# efr32_vna.net
KiCad netlist of a schematic drawn in Altium Designer
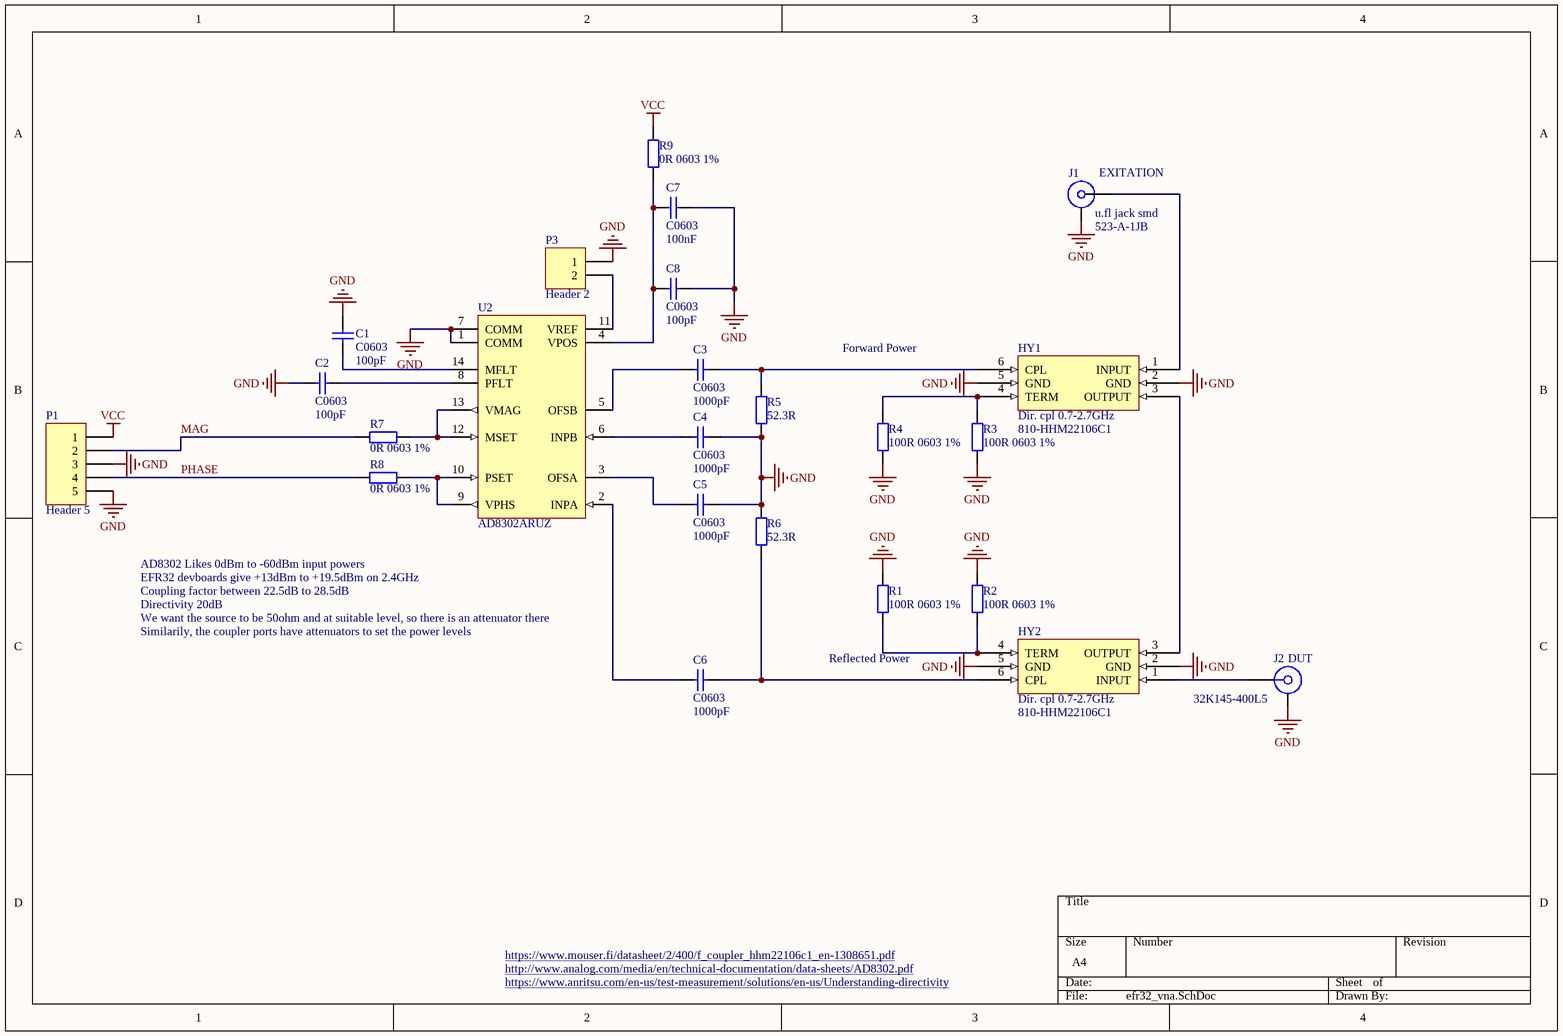
[diagram p0: efr32_vna.SchDoc]

(export (version "E")
  (design (tool "Eeschema 10.0.6"))
  (components
    (comp (ref "C1")
      (value "C0603")
      (footprint "0603")
      (description "Ceramic Chip Capacitor - Standard")
      (fields (field (name "ALTIUM_VALUE") "100pF") (field (name "PUBLISHER") "Altium Limited"))
      (libsource (lib "KEMET Chip Capacitor") (part "C0603"))
    )
    (comp (ref "C2")
      (value "C0603")
      (footprint "0603")
      (description "Ceramic Chip Capacitor - Standard")
      (fields (field (name "ALTIUM_VALUE") "100pF") (field (name "PUBLISHER") "Altium Limited"))
      (libsource (lib "KEMET Chip Capacitor") (part "C0603"))
    )
    (comp (ref "C3")
      (value "C0603")
      (footprint "0603")
      (description "Ceramic Chip Capacitor - Standard")
      (fields (field (name "ALTIUM_VALUE") "1000pF") (field (name "PUBLISHER") "Altium Limited"))
      (libsource (lib "KEMET Chip Capacitor") (part "C0603"))
    )
    (comp (ref "C4")
      (value "C0603")
      (footprint "0603")
      (description "Ceramic Chip Capacitor - Standard")
      (fields (field (name "ALTIUM_VALUE") "1000pF") (field (name "PUBLISHER") "Altium Limited"))
      (libsource (lib "KEMET Chip Capacitor") (part "C0603"))
    )
    (comp (ref "C5")
      (value "C0603")
      (footprint "0603")
      (description "Ceramic Chip Capacitor - Standard")
      (fields (field (name "ALTIUM_VALUE") "1000pF") (field (name "PUBLISHER") "Altium Limited"))
      (libsource (lib "KEMET Chip Capacitor") (part "C0603"))
    )
    (comp (ref "C6")
      (value "C0603")
      (footprint "0603")
      (description "Ceramic Chip Capacitor - Standard")
      (fields (field (name "ALTIUM_VALUE") "1000pF") (field (name "PUBLISHER") "Altium Limited"))
      (libsource (lib "KEMET Chip Capacitor") (part "C0603"))
    )
    (comp (ref "C7")
      (value "C0603")
      (footprint "0603")
      (description "Ceramic Chip Capacitor - Standard")
      (fields (field (name "ALTIUM_VALUE") "100nF") (field (name "PUBLISHER") "Altium Limited"))
      (libsource (lib "KEMET Chip Capacitor") (part "C0603"))
    )
    (comp (ref "C8")
      (value "C0603")
      (footprint "0603")
      (description "Ceramic Chip Capacitor - Standard")
      (fields (field (name "ALTIUM_VALUE") "100pF") (field (name "PUBLISHER") "Altium Limited"))
      (libsource (lib "KEMET Chip Capacitor") (part "C0603"))
    )
    (comp (ref "HY1")
      (value "Dir. cpl 0.7-2.7GHz")
      (footprint "1.6x0.8mm [EIA 0603]")
      (description "0.7-2.7GHz 28.5dB directional coupler")
      (fields (field (name "SUPPLIER PART NUMBER 1") "810-HHM22106C1"))
      (libsource (lib "") (part "HHM22106C1_1"))
    )
    (comp (ref "HY2")
      (value "Dir. cpl 0.7-2.7GHz")
      (footprint "1.6x0.8mm [EIA 0603]")
      (description "0.7-2.7GHz 28.5dB directional coupler")
      (fields (field (name "SUPPLIER PART NUMBER 1") "810-HHM22106C1"))
      (libsource (lib "ftg_lib") (part "HHM22106C1"))
    )
    (comp (ref "J1")
      (value "u.fl jack smd")
      (footprint "U.FL jack")
      (fields (field (name "SUPPLIER PART NUMBER 1") "523-A-1JB"))
      (libsource (lib "ftg_lib") (part "u.fl connector, jack A-1JB"))
    )
    (comp (ref "J2")
      (value "32K145-400L5")
      (footprint "ROS-32K145-400L5_V")
      (description "SMA Right Angle Jack, Edge Mount, Up to 18 GHz, -55 to 155 degC")
      (libsource (lib "Rosenberger SMA") (part "32K145-400L5"))
    )
    (comp (ref "P1")
      (value "Header 5")
      (footprint "HDR1X5")
      (description "Header, 5-Pin")
      (fields (field (name "PUBLISHER") "Altium Limited"))
      (libsource (lib "Miscellaneous Connectors") (part "Header 5"))
    )
    (comp (ref "P3")
      (value "Header 2")
      (footprint "HDR1X2")
      (description "Header, 2-Pin")
      (fields (field (name "PUBLISHER") "Altium Limited"))
      (libsource (lib "Miscellaneous Connectors") (part "Header 2"))
    )
    (comp (ref "R1")
      (value "100R 0603 1%")
      (footprint "R0603")
      (fields (field (name "TOLERANCE") "1%") (field (name "PUBLISHER") "iv"))
      (libsource (lib "ftg_lib") (part "100R 0603"))
    )
    (comp (ref "R2")
      (value "100R 0603 1%")
      (footprint "R0603")
      (fields (field (name "TOLERANCE") "1%") (field (name "PUBLISHER") "iv"))
      (libsource (lib "ftg_lib") (part "100R 0603"))
    )
    (comp (ref "R3")
      (value "100R 0603 1%")
      (footprint "R0603")
      (fields (field (name "TOLERANCE") "1%") (field (name "PUBLISHER") "iv"))
      (libsource (lib "") (part "100R 0603_1"))
    )
    (comp (ref "R4")
      (value "100R 0603 1%")
      (footprint "R0603")
      (fields (field (name "TOLERANCE") "1%") (field (name "PUBLISHER") "iv"))
      (libsource (lib "") (part "100R 0603_1"))
    )
    (comp (ref "R5")
      (value "52.3R")
      (footprint "R0603")
      (description "100R 0603 1%")
      (fields (field (name "TOLERANCE") "1%") (field (name "PUBLISHER") "iv"))
      (libsource (lib "ftg_lib") (part "100R 0603"))
    )
    (comp (ref "R6")
      (value "52.3R")
      (footprint "R0603")
      (description "100R 0603 1%")
      (fields (field (name "TOLERANCE") "1%") (field (name "PUBLISHER") "iv"))
      (libsource (lib "ftg_lib") (part "100R 0603"))
    )
    (comp (ref "R7")
      (value "0R 0603 1%")
      (footprint "R0603")
      (fields (field (name "TOLERANCE") "1%") (field (name "PUBLISHER") "iv"))
      (libsource (lib "ftg_lib") (part "0R 0603"))
    )
    (comp (ref "R8")
      (value "0R 0603 1%")
      (footprint "R0603")
      (fields (field (name "TOLERANCE") "1%") (field (name "PUBLISHER") "iv"))
      (libsource (lib "ftg_lib") (part "0R 0603"))
    )
    (comp (ref "R9")
      (value "0R 0603 1%")
      (footprint "R0603")
      (fields (field (name "TOLERANCE") "1%") (field (name "PUBLISHER") "iv"))
      (libsource (lib "") (part "0R 0603_1"))
    )
    (comp (ref "U2")
      (value "AD8302ARUZ")
      (footprint "ADI-RU-14_M")
      (description "LF-2.7 GHz RF/IF Gain and Phase Detector, 60ns Response Time, RU-14, Pb-Free, 96 Tube")
      (libsource (lib "Altium Content Vault") (part "ADI-AD8302-RU-14"))
    )
  )
  (nets
    (net (code "1") (name "/MAG") (class "Default")
      (node (ref "P1") (pin "2") (pinfunction "2_2") (pintype "passive"))
      (node (ref "R7") (pin "1") (pinfunction "1_1") (pintype "passive"))
    )
    (net (code "2") (name "/PHASE") (class "Default")
      (node (ref "P1") (pin "4") (pinfunction "4_4") (pintype "passive"))
      (node (ref "R8") (pin "1") (pinfunction "1_1") (pintype "passive"))
    )
    (net (code "3") (name "GND") (class "Default")
      (node (ref "C1") (pin "2") (pinfunction "2_2") (pintype "passive"))
      (node (ref "C2") (pin "1") (pinfunction "1_1") (pintype "passive"))
      (node (ref "C4") (pin "2") (pinfunction "2_2") (pintype "passive"))
      (node (ref "C5") (pin "2") (pinfunction "2_2") (pintype "passive"))
      (node (ref "C7") (pin "2") (pinfunction "2_2") (pintype "passive"))
      (node (ref "C8") (pin "2") (pinfunction "2_2") (pintype "passive"))
      (node (ref "HY1") (pin "2") (pinfunction "GND_2") (pintype "input"))
      (node (ref "HY1") (pin "5") (pinfunction "GND_5") (pintype "input"))
      (node (ref "HY2") (pin "2") (pinfunction "GND_2") (pintype "input"))
      (node (ref "HY2") (pin "5") (pinfunction "GND_5") (pintype "input"))
      (node (ref "J1") (pin "2") (pinfunction "2_2") (pintype "passive"))
      (node (ref "J2") (pin "MP") (pinfunction "MP_MP") (pintype "passive"))
      (node (ref "P1") (pin "3") (pinfunction "3_3") (pintype "passive"))
      (node (ref "P1") (pin "5") (pinfunction "5_5") (pintype "passive"))
      (node (ref "P3") (pin "1") (pinfunction "1_1") (pintype "passive"))
      (node (ref "R1") (pin "1") (pinfunction "1_1") (pintype "passive"))
      (node (ref "R2") (pin "1") (pinfunction "1_1") (pintype "passive"))
      (node (ref "R3") (pin "1") (pinfunction "1_1") (pintype "passive"))
      (node (ref "R4") (pin "1") (pinfunction "1_1") (pintype "passive"))
      (node (ref "R5") (pin "2") (pinfunction "2_2") (pintype "passive"))
      (node (ref "R6") (pin "1") (pinfunction "1_1") (pintype "passive"))
      (node (ref "U2") (pin "1") (pinfunction "COMM_1") (pintype "power_in"))
      (node (ref "U2") (pin "7") (pinfunction "COMM_7") (pintype "power_in"))
    )
    (net (code "4") (name "Net-(HY1-CPL)") (class "Default")
      (node (ref "C3") (pin "2") (pinfunction "2_2") (pintype "passive"))
      (node (ref "HY1") (pin "6") (pinfunction "CPL_6") (pintype "input"))
      (node (ref "R5") (pin "1") (pinfunction "1_1") (pintype "passive"))
    )
    (net (code "5") (name "Net-(HY1-INPUT)") (class "Default")
      (node (ref "HY1") (pin "1") (pinfunction "INPUT_1") (pintype "input"))
      (node (ref "J1") (pin "1") (pinfunction "1_1") (pintype "passive"))
    )
    (net (code "6") (name "Net-(HY1-OUTPUT)") (class "Default")
      (node (ref "HY1") (pin "3") (pinfunction "OUTPUT_3") (pintype "input"))
      (node (ref "HY2") (pin "3") (pinfunction "OUTPUT_3") (pintype "input"))
    )
    (net (code "7") (name "Net-(HY1-TERM)") (class "Default")
      (node (ref "HY1") (pin "4") (pinfunction "TERM_4") (pintype "input"))
      (node (ref "R3") (pin "2") (pinfunction "2_2") (pintype "passive"))
      (node (ref "R4") (pin "2") (pinfunction "2_2") (pintype "passive"))
    )
    (net (code "8") (name "Net-(HY2-CPL)") (class "Default")
      (node (ref "C6") (pin "2") (pinfunction "2_2") (pintype "passive"))
      (node (ref "HY2") (pin "6") (pinfunction "CPL_6") (pintype "input"))
      (node (ref "R6") (pin "2") (pinfunction "2_2") (pintype "passive"))
    )
    (net (code "9") (name "Net-(HY2-INPUT)") (class "Default")
      (node (ref "HY2") (pin "1") (pinfunction "INPUT_1") (pintype "input"))
      (node (ref "J2") (pin "1") (pinfunction "1_1") (pintype "passive"))
    )
    (net (code "10") (name "Net-(HY2-TERM)") (class "Default")
      (node (ref "HY2") (pin "4") (pinfunction "TERM_4") (pintype "input"))
      (node (ref "R1") (pin "2") (pinfunction "2_2") (pintype "passive"))
      (node (ref "R2") (pin "2") (pinfunction "2_2") (pintype "passive"))
    )
    (net (code "11") (name "Net-(U2-INPA)") (class "Default")
      (node (ref "C6") (pin "1") (pinfunction "1_1") (pintype "passive"))
      (node (ref "U2") (pin "2") (pinfunction "INPA_2") (pintype "input"))
    )
    (net (code "12") (name "Net-(U2-INPB)") (class "Default")
      (node (ref "C4") (pin "1") (pinfunction "1_1") (pintype "passive"))
      (node (ref "U2") (pin "6") (pinfunction "INPB_6") (pintype "input"))
    )
    (net (code "13") (name "Net-(U2-MFLT)") (class "Default")
      (node (ref "C1") (pin "1") (pinfunction "1_1") (pintype "passive"))
      (node (ref "U2") (pin "14") (pinfunction "MFLT_14") (pintype "passive"))
    )
    (net (code "14") (name "Net-(U2-MSET)") (class "Default")
      (node (ref "R7") (pin "2") (pinfunction "2_2") (pintype "passive"))
      (node (ref "U2") (pin "12") (pinfunction "MSET_12") (pintype "input"))
      (node (ref "U2") (pin "13") (pinfunction "VMAG_13") (pintype "output"))
    )
    (net (code "15") (name "Net-(U2-OFSA)") (class "Default")
      (node (ref "C5") (pin "1") (pinfunction "1_1") (pintype "passive"))
      (node (ref "U2") (pin "3") (pinfunction "OFSA_3") (pintype "passive"))
    )
    (net (code "16") (name "Net-(U2-OFSB)") (class "Default")
      (node (ref "C3") (pin "1") (pinfunction "1_1") (pintype "passive"))
      (node (ref "U2") (pin "5") (pinfunction "OFSB_5") (pintype "passive"))
    )
    (net (code "17") (name "Net-(U2-PFLT)") (class "Default")
      (node (ref "C2") (pin "2") (pinfunction "2_2") (pintype "passive"))
      (node (ref "U2") (pin "8") (pinfunction "PFLT_8") (pintype "passive"))
    )
    (net (code "18") (name "Net-(U2-PSET)") (class "Default")
      (node (ref "R8") (pin "2") (pinfunction "2_2") (pintype "passive"))
      (node (ref "U2") (pin "10") (pinfunction "PSET_10") (pintype "input"))
      (node (ref "U2") (pin "9") (pinfunction "VPHS_9") (pintype "output"))
    )
    (net (code "19") (name "Net-(U2-VPOS)") (class "Default")
      (node (ref "C7") (pin "1") (pinfunction "1_1") (pintype "passive"))
      (node (ref "C8") (pin "1") (pinfunction "1_1") (pintype "passive"))
      (node (ref "R9") (pin "1") (pinfunction "1_1") (pintype "passive"))
      (node (ref "U2") (pin "4") (pinfunction "VPOS_4") (pintype "power_in"))
    )
    (net (code "20") (name "Net-(U2-VREF)") (class "Default")
      (node (ref "P3") (pin "2") (pinfunction "2_2") (pintype "passive"))
      (node (ref "U2") (pin "11") (pinfunction "VREF_11") (pintype "power_in"))
    )
    (net (code "21") (name "VCC") (class "Default")
      (node (ref "P1") (pin "1") (pinfunction "1_1") (pintype "passive"))
      (node (ref "R9") (pin "2") (pinfunction "2_2") (pintype "passive"))
    )
  )
)
